# ESP32.net
KiCad netlist of a schematic drawn in EAGLE
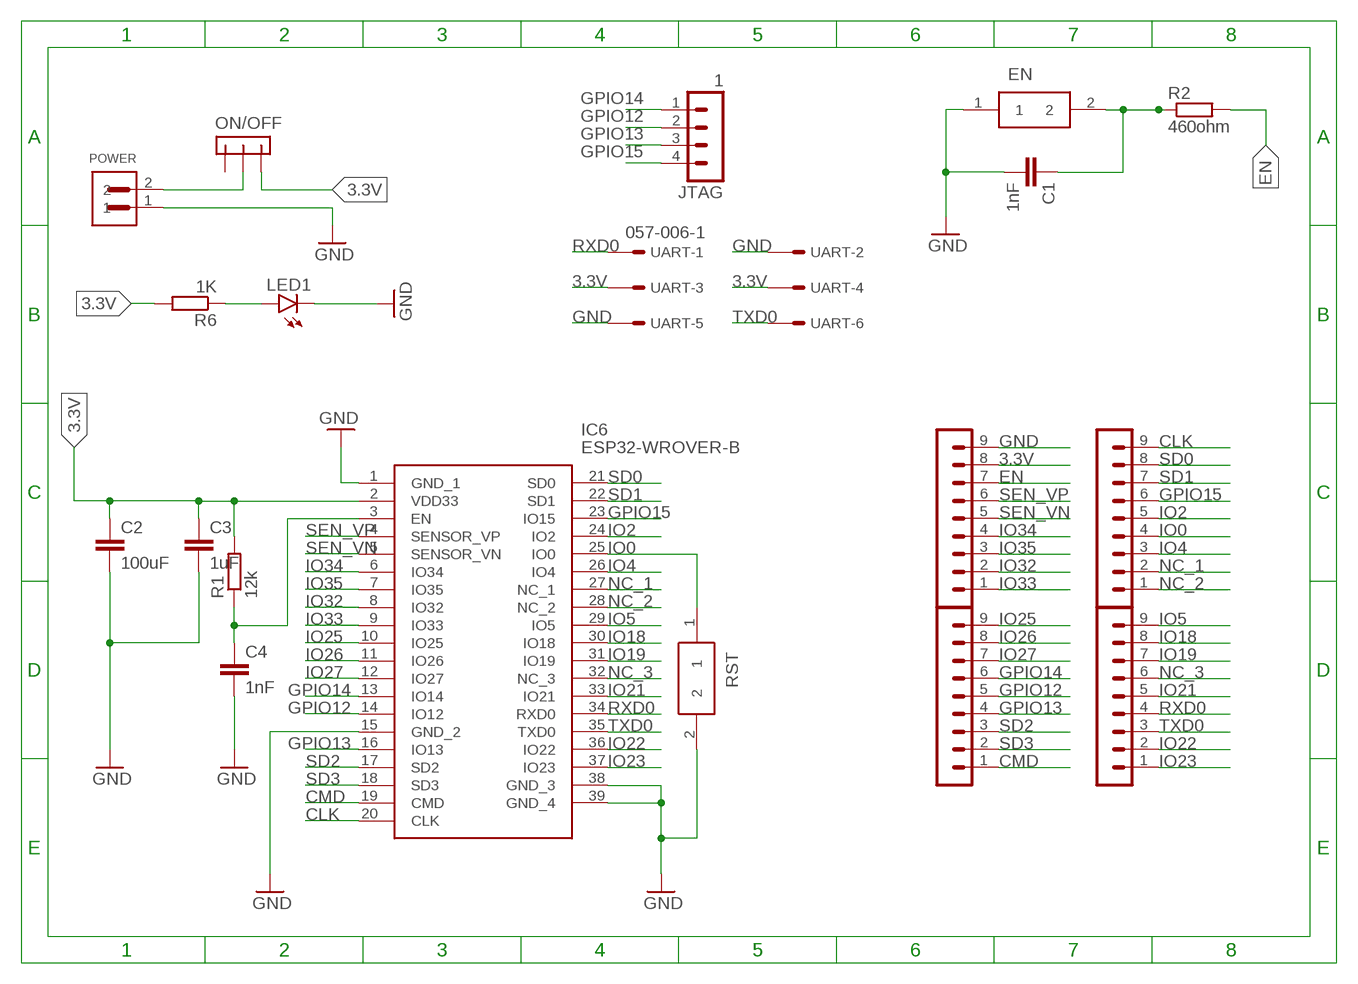
[diagram p0: schematic, sheet 1]

(export (version "E")
  (design (tool "Eeschema 10.0.6"))
  (components
    (comp (ref "C1")
      (value "1nF")
      (footprint "eagle-import:C0805")
      (libsource (lib "eagle-import") (part "C-EU_805C0805"))
    )
    (comp (ref "C2")
      (value "100uF")
      (footprint "eagle-import:C1206")
      (libsource (lib "eagle-import") (part "C-EU_1206C1206"))
    )
    (comp (ref "C3")
      (value "1uF")
      (footprint "eagle-import:C0805")
      (libsource (lib "eagle-import") (part "C-EU_805C0805"))
    )
    (comp (ref "C4")
      (value "1nF")
      (footprint "eagle-import:C0805")
      (libsource (lib "eagle-import") (part "C-EU_805C0805"))
    )
    (comp (ref "EN")
      (value "FSMSMTR")
      (footprint "eagle-import:FSMSM")
      (fields (field (name "MOUSER_PART_NUMBER") "506-FSMSMTR") (field (name "RS_PART_NUMBER") "1680547"))
      (libsource (lib "eagle-import") (part "FSMSMTR"))
    )
    (comp (ref "IC6")
      (value "ESP32-WROVER-B")
      (footprint "eagle-import:ESP32WROVERIB16MB")
      (fields (field (name "MOUSER_PART_NUMBER") "356-ESP32-WROVER-B"))
      (libsource (lib "eagle-import") (part "ESP32-WROVER-B"))
    )
    (comp (ref "JTAG")
      (value "1")
      (footprint "eagle-import:MA04-1")
      (libsource (lib "eagle-import") (part "MA04-1"))
    )
    (comp (ref "LED1")
      (value "LEDSMT1206")
      (footprint "eagle-import:1206")
      (libsource (lib "eagle-import") (part "LEDSMT1206"))
    )
    (comp (ref "ON/OFF")
      (value "-CON3")
      (footprint "eagle-import:CON3")
      (libsource (lib "eagle-import") (part "-CON3"))
    )
    (comp (ref "POWER")
      (value "S2B-PH-SM4-TB")
      (footprint "eagle-import:JST_S2B-PH-SM4-TB")
      (fields (field (name "MF") "JST Sales"))
      (libsource (lib "eagle-import") (part "S2B-PH-SM4-TB"))
    )
    (comp (ref "R1")
      (value "12k")
      (footprint "eagle-import:R0805")
      (libsource (lib "eagle-import") (part "R-EU_805R0805"))
    )
    (comp (ref "R2")
      (value "460ohm")
      (footprint "eagle-import:R0805")
      (libsource (lib "eagle-import") (part "R-EU_805R0805"))
    )
    (comp (ref "R6")
      (value "1K")
      (footprint "eagle-import:R1206")
      (libsource (lib "eagle-import") (part "R-EU_R1206"))
    )
    (comp (ref "RST")
      (value "FSMSMTR")
      (footprint "eagle-import:FSMSM")
      (fields (field (name "MOUSER_PART_NUMBER") "506-FSMSMTR") (field (name "RS_PART_NUMBER") "1680547"))
      (libsource (lib "eagle-import") (part "FSMSMTR"))
    )
    (comp (ref "SV1")
      (value "PINHEADER-1X9")
      (footprint "eagle-import:MA09-1")
      (libsource (lib "eagle-import") (part "PINHEADER-1X9"))
    )
    (comp (ref "SV2")
      (value "PINHEADER-1X9")
      (footprint "eagle-import:MA09-1")
      (libsource (lib "eagle-import") (part "PINHEADER-1X9"))
    )
    (comp (ref "SV5")
      (value "PINHEADER-1X9")
      (footprint "eagle-import:MA09-1")
      (libsource (lib "eagle-import") (part "PINHEADER-1X9"))
    )
    (comp (ref "SV6")
      (value "PINHEADER-1X9")
      (footprint "eagle-import:MA09-1")
      (libsource (lib "eagle-import") (part "PINHEADER-1X9"))
    )
    (comp (ref "UART")
      (value "057-006-1")
      (footprint "eagle-import:057-006-1")
      (libsource (lib "eagle-import") (part "057-006-1"))
    )
  )
  (nets
    (net (code "1") (name "3.3V") (class "Default")
      (node (ref "C2") (pin "1") (pinfunction "1_1") (pintype "passive"))
      (node (ref "C3") (pin "1") (pinfunction "1_1") (pintype "passive"))
      (node (ref "IC6") (pin "2") (pinfunction "VDD33_2") (pintype "bidirectional"))
      (node (ref "ON/OFF") (pin "P$1") (pinfunction "1_P$1") (pintype "passive"))
      (node (ref "R1") (pin "2") (pinfunction "2_2") (pintype "passive"))
      (node (ref "R6") (pin "2") (pinfunction "2_2") (pintype "passive"))
      (node (ref "SV5") (pin "8") (pinfunction "8_8") (pintype "passive"))
      (node (ref "UART") (pin "3") (pinfunction "S_3") (pintype "passive"))
      (node (ref "UART") (pin "4") (pinfunction "S_4") (pintype "passive"))
    )
    (net (code "2") (name "CLK") (class "Default")
      (node (ref "IC6") (pin "20") (pinfunction "CLK_20") (pintype "bidirectional"))
      (node (ref "SV1") (pin "9") (pinfunction "9_9") (pintype "passive"))
    )
    (net (code "3") (name "CMD") (class "Default")
      (node (ref "IC6") (pin "19") (pinfunction "CMD_19") (pintype "bidirectional"))
      (node (ref "SV6") (pin "1") (pinfunction "1_1") (pintype "passive"))
    )
    (net (code "4") (name "EN") (class "Default")
      (node (ref "C1") (pin "1") (pinfunction "1_1") (pintype "passive"))
      (node (ref "C4") (pin "1") (pinfunction "1_1") (pintype "passive"))
      (node (ref "EN") (pin "2") (pinfunction "2_2") (pintype "bidirectional"))
      (node (ref "IC6") (pin "3") (pinfunction "EN_3") (pintype "bidirectional"))
      (node (ref "R1") (pin "1") (pinfunction "1_1") (pintype "passive"))
      (node (ref "R2") (pin "1") (pinfunction "1_1") (pintype "passive"))
      (node (ref "R2") (pin "2") (pinfunction "2_2") (pintype "passive"))
      (node (ref "SV5") (pin "7") (pinfunction "7_7") (pintype "passive"))
    )
    (net (code "5") (name "GND") (class "Default")
      (node (ref "C1") (pin "2") (pinfunction "2_2") (pintype "passive"))
      (node (ref "C2") (pin "2") (pinfunction "2_2") (pintype "passive"))
      (node (ref "C3") (pin "2") (pinfunction "2_2") (pintype "passive"))
      (node (ref "C4") (pin "2") (pinfunction "2_2") (pintype "passive"))
      (node (ref "EN") (pin "1") (pinfunction "1_1") (pintype "bidirectional"))
      (node (ref "IC6") (pin "1") (pinfunction "GND_1_1") (pintype "bidirectional"))
      (node (ref "IC6") (pin "15") (pinfunction "GND_2_15") (pintype "bidirectional"))
      (node (ref "IC6") (pin "38") (pinfunction "GND_3_38") (pintype "bidirectional"))
      (node (ref "IC6") (pin "39") (pinfunction "GND_4_39") (pintype "bidirectional"))
      (node (ref "LED1") (pin "C") (pinfunction "C_C") (pintype "passive"))
      (node (ref "POWER") (pin "1") (pinfunction "1_1") (pintype "passive"))
      (node (ref "RST") (pin "2") (pinfunction "2_2") (pintype "bidirectional"))
      (node (ref "SV5") (pin "9") (pinfunction "9_9") (pintype "passive"))
      (node (ref "UART") (pin "2") (pinfunction "S_2") (pintype "passive"))
      (node (ref "UART") (pin "5") (pinfunction "S_5") (pintype "passive"))
    )
    (net (code "6") (name "GPIO12") (class "Default")
      (node (ref "IC6") (pin "14") (pinfunction "IO12_14") (pintype "bidirectional"))
      (node (ref "JTAG") (pin "2") (pinfunction "2_2") (pintype "passive"))
      (node (ref "SV6") (pin "5") (pinfunction "5_5") (pintype "passive"))
    )
    (net (code "7") (name "GPIO13") (class "Default")
      (node (ref "IC6") (pin "16") (pinfunction "IO13_16") (pintype "bidirectional"))
      (node (ref "JTAG") (pin "3") (pinfunction "3_3") (pintype "passive"))
      (node (ref "SV6") (pin "4") (pinfunction "4_4") (pintype "passive"))
    )
    (net (code "8") (name "GPIO14") (class "Default")
      (node (ref "IC6") (pin "13") (pinfunction "IO14_13") (pintype "bidirectional"))
      (node (ref "JTAG") (pin "1") (pinfunction "1_1") (pintype "passive"))
      (node (ref "SV6") (pin "6") (pinfunction "6_6") (pintype "passive"))
    )
    (net (code "9") (name "GPIO15") (class "Default")
      (node (ref "IC6") (pin "23") (pinfunction "IO15_23") (pintype "bidirectional"))
      (node (ref "JTAG") (pin "4") (pinfunction "4_4") (pintype "passive"))
      (node (ref "SV1") (pin "6") (pinfunction "6_6") (pintype "passive"))
    )
    (net (code "10") (name "IO0") (class "Default")
      (node (ref "IC6") (pin "25") (pinfunction "IO0_25") (pintype "bidirectional"))
      (node (ref "RST") (pin "1") (pinfunction "1_1") (pintype "bidirectional"))
      (node (ref "SV1") (pin "4") (pinfunction "4_4") (pintype "passive"))
    )
    (net (code "11") (name "IO2") (class "Default")
      (node (ref "IC6") (pin "24") (pinfunction "IO2_24") (pintype "bidirectional"))
      (node (ref "SV1") (pin "5") (pinfunction "5_5") (pintype "passive"))
    )
    (net (code "12") (name "IO4") (class "Default")
      (node (ref "IC6") (pin "26") (pinfunction "IO4_26") (pintype "bidirectional"))
      (node (ref "SV1") (pin "3") (pinfunction "3_3") (pintype "passive"))
    )
    (net (code "13") (name "IO5") (class "Default")
      (node (ref "IC6") (pin "29") (pinfunction "IO5_29") (pintype "bidirectional"))
      (node (ref "SV2") (pin "9") (pinfunction "9_9") (pintype "passive"))
    )
    (net (code "14") (name "IO18") (class "Default")
      (node (ref "IC6") (pin "30") (pinfunction "IO18_30") (pintype "bidirectional"))
      (node (ref "SV2") (pin "8") (pinfunction "8_8") (pintype "passive"))
    )
    (net (code "15") (name "IO19") (class "Default")
      (node (ref "IC6") (pin "31") (pinfunction "IO19_31") (pintype "bidirectional"))
      (node (ref "SV2") (pin "7") (pinfunction "7_7") (pintype "passive"))
    )
    (net (code "16") (name "IO21") (class "Default")
      (node (ref "IC6") (pin "33") (pinfunction "IO21_33") (pintype "bidirectional"))
      (node (ref "SV2") (pin "5") (pinfunction "5_5") (pintype "passive"))
    )
    (net (code "17") (name "IO22") (class "Default")
      (node (ref "IC6") (pin "36") (pinfunction "IO22_36") (pintype "bidirectional"))
      (node (ref "SV2") (pin "2") (pinfunction "2_2") (pintype "passive"))
    )
    (net (code "18") (name "IO23") (class "Default")
      (node (ref "IC6") (pin "37") (pinfunction "IO23_37") (pintype "bidirectional"))
      (node (ref "SV2") (pin "1") (pinfunction "1_1") (pintype "passive"))
    )
    (net (code "19") (name "IO25") (class "Default")
      (node (ref "IC6") (pin "10") (pinfunction "IO25_10") (pintype "bidirectional"))
      (node (ref "SV6") (pin "9") (pinfunction "9_9") (pintype "passive"))
    )
    (net (code "20") (name "IO26") (class "Default")
      (node (ref "IC6") (pin "11") (pinfunction "IO26_11") (pintype "bidirectional"))
      (node (ref "SV6") (pin "8") (pinfunction "8_8") (pintype "passive"))
    )
    (net (code "21") (name "IO27") (class "Default")
      (node (ref "IC6") (pin "12") (pinfunction "IO27_12") (pintype "bidirectional"))
      (node (ref "SV6") (pin "7") (pinfunction "7_7") (pintype "passive"))
    )
    (net (code "22") (name "IO32") (class "Default")
      (node (ref "IC6") (pin "8") (pinfunction "IO32_8") (pintype "bidirectional"))
      (node (ref "SV5") (pin "2") (pinfunction "2_2") (pintype "passive"))
    )
    (net (code "23") (name "IO33") (class "Default")
      (node (ref "IC6") (pin "9") (pinfunction "IO33_9") (pintype "bidirectional"))
      (node (ref "SV5") (pin "1") (pinfunction "1_1") (pintype "passive"))
    )
    (net (code "24") (name "IO34") (class "Default")
      (node (ref "IC6") (pin "6") (pinfunction "IO34_6") (pintype "bidirectional"))
      (node (ref "SV5") (pin "4") (pinfunction "4_4") (pintype "passive"))
    )
    (net (code "25") (name "IO35") (class "Default")
      (node (ref "IC6") (pin "7") (pinfunction "IO35_7") (pintype "bidirectional"))
      (node (ref "SV5") (pin "3") (pinfunction "3_3") (pintype "passive"))
    )
    (net (code "26") (name "NC_1") (class "Default")
      (node (ref "IC6") (pin "27") (pinfunction "NC_1_27") (pintype "bidirectional"))
      (node (ref "SV1") (pin "2") (pinfunction "2_2") (pintype "passive"))
    )
    (net (code "27") (name "NC_2") (class "Default")
      (node (ref "IC6") (pin "28") (pinfunction "NC_2_28") (pintype "bidirectional"))
      (node (ref "SV1") (pin "1") (pinfunction "1_1") (pintype "passive"))
    )
    (net (code "28") (name "NC_3") (class "Default")
      (node (ref "IC6") (pin "32") (pinfunction "NC_3_32") (pintype "bidirectional"))
      (node (ref "SV2") (pin "6") (pinfunction "6_6") (pintype "passive"))
    )
    (net (code "29") (name "Net-(LED1-PadA)") (class "Default")
      (node (ref "LED1") (pin "A") (pinfunction "A_A") (pintype "passive"))
      (node (ref "R6") (pin "1") (pinfunction "1_1") (pintype "passive"))
    )
    (net (code "30") (name "Net-(ON/OFF-2)") (class "Default")
      (node (ref "ON/OFF") (pin "P$2") (pinfunction "2_P$2") (pintype "passive"))
      (node (ref "POWER") (pin "2") (pinfunction "2_2") (pintype "passive"))
    )
    (net (code "31") (name "RXD0") (class "Default")
      (node (ref "IC6") (pin "34") (pinfunction "RXD0_34") (pintype "bidirectional"))
      (node (ref "SV2") (pin "4") (pinfunction "4_4") (pintype "passive"))
      (node (ref "UART") (pin "1") (pinfunction "S_1") (pintype "passive"))
    )
    (net (code "32") (name "SD0") (class "Default")
      (node (ref "IC6") (pin "21") (pinfunction "SD0_21") (pintype "bidirectional"))
      (node (ref "SV1") (pin "8") (pinfunction "8_8") (pintype "passive"))
    )
    (net (code "33") (name "SD1") (class "Default")
      (node (ref "IC6") (pin "22") (pinfunction "SD1_22") (pintype "bidirectional"))
      (node (ref "SV1") (pin "7") (pinfunction "7_7") (pintype "passive"))
    )
    (net (code "34") (name "SD2") (class "Default")
      (node (ref "IC6") (pin "17") (pinfunction "SD2_17") (pintype "bidirectional"))
      (node (ref "SV6") (pin "3") (pinfunction "3_3") (pintype "passive"))
    )
    (net (code "35") (name "SD3") (class "Default")
      (node (ref "IC6") (pin "18") (pinfunction "SD3_18") (pintype "bidirectional"))
      (node (ref "SV6") (pin "2") (pinfunction "2_2") (pintype "passive"))
    )
    (net (code "36") (name "SEN_VN") (class "Default")
      (node (ref "IC6") (pin "5") (pinfunction "SENSOR_VN_5") (pintype "bidirectional"))
      (node (ref "SV5") (pin "5") (pinfunction "5_5") (pintype "passive"))
    )
    (net (code "37") (name "SEN_VP") (class "Default")
      (node (ref "IC6") (pin "4") (pinfunction "SENSOR_VP_4") (pintype "bidirectional"))
      (node (ref "SV5") (pin "6") (pinfunction "6_6") (pintype "passive"))
    )
    (net (code "38") (name "TXD0") (class "Default")
      (node (ref "IC6") (pin "35") (pinfunction "TXD0_35") (pintype "bidirectional"))
      (node (ref "SV2") (pin "3") (pinfunction "3_3") (pintype "passive"))
      (node (ref "UART") (pin "6") (pinfunction "S_6") (pintype "passive"))
    )
    (net (code "39") (name "unconnected-(ON/OFF-3-PadP$3)") (class "Default")
      (node (ref "ON/OFF") (pin "P$3") (pinfunction "3_P$3") (pintype "passive"))
    )
  )
)
